# 7333.net
KiCad netlist of a schematic drawn in EAGLE
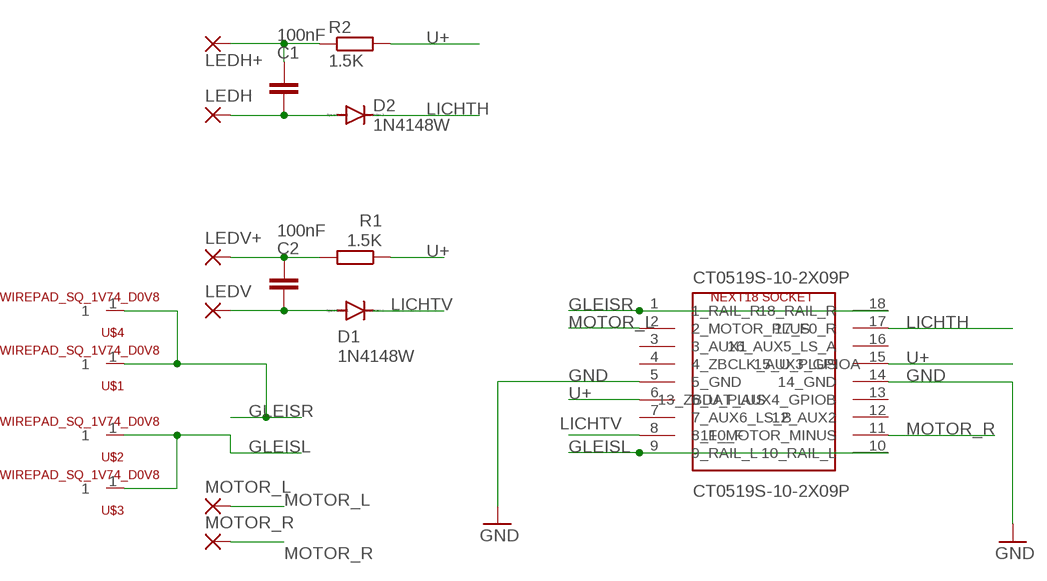
[diagram p0: schematic, sheet 1]

(export (version "E")
  (design (tool "Eeschema 10.0.6"))
  (components
    (comp (ref "C1")
      (value "100nF")
      (footprint "eagle-import:C0805")
      (libsource (lib "eagle-import") (part "C-EUC0805"))
    )
    (comp (ref "C2")
      (value "100nF")
      (footprint "eagle-import:C0805")
      (libsource (lib "eagle-import") (part "C-EUC0805"))
    )
    (comp (ref "CT0519S-10-2X09P")
      (value "CT0519S-10-2X09P")
      (footprint "eagle-import:NEXT18_SOCKET_GENERIC_VERIFY")
      (libsource (lib "eagle-import") (part "NEXT18_SOCKET-GENERIC-VERIFY"))
    )
    (comp (ref "D1")
      (value "1N4148W")
      (footprint "eagle-import:SOD123")
      (libsource (lib "eagle-import") (part "DIODE-SOD123"))
    )
    (comp (ref "D2")
      (value "1N4148W")
      (footprint "eagle-import:SOD123")
      (libsource (lib "eagle-import") (part "DIODE-SOD123"))
    )
    (comp (ref "LEDH")
      (value "SMD2")
      (footprint "eagle-import:SMD1,27-2,54")
      (libsource (lib "eagle-import") (part "SMD2"))
    )
    (comp (ref "LEDH+")
      (value "SMD2")
      (footprint "eagle-import:SMD1,27-2,54")
      (libsource (lib "eagle-import") (part "SMD2"))
    )
    (comp (ref "LEDV")
      (value "SMD2")
      (footprint "eagle-import:SMD1,27-2,54")
      (libsource (lib "eagle-import") (part "SMD2"))
    )
    (comp (ref "LEDV+")
      (value "SMD2")
      (footprint "eagle-import:SMD1,27-2,54")
      (libsource (lib "eagle-import") (part "SMD2"))
    )
    (comp (ref "MOTOR_L")
      (value "SMD5")
      (footprint "eagle-import:SMD2,54-5,08")
      (libsource (lib "eagle-import") (part "SMD5"))
    )
    (comp (ref "MOTOR_R")
      (value "SMD5")
      (footprint "eagle-import:SMD2,54-5,08")
      (libsource (lib "eagle-import") (part "SMD5"))
    )
    (comp (ref "R1")
      (value "1.5K")
      (footprint "eagle-import:M0805")
      (libsource (lib "eagle-import") (part "R-EU_M0805"))
    )
    (comp (ref "R2")
      (value "1.5K")
      (footprint "eagle-import:M0805")
      (libsource (lib "eagle-import") (part "R-EU_M0805"))
    )
    (comp (ref "U$1")
      (value "WIREPAD_SQ_1V74_D0V8")
      (footprint "eagle-import:WIREPAD_SQ_1V74_D0V8")
      (libsource (lib "eagle-import") (part "WIREPAD_SQ_1V74_D0V8"))
    )
    (comp (ref "U$2")
      (value "WIREPAD_SQ_1V74_D0V8")
      (footprint "eagle-import:WIREPAD_SQ_1V74_D0V8")
      (libsource (lib "eagle-import") (part "WIREPAD_SQ_1V74_D0V8"))
    )
    (comp (ref "U$3")
      (value "WIREPAD_SQ_1V74_D0V8")
      (footprint "eagle-import:WIREPAD_SQ_1V74_D0V8")
      (libsource (lib "eagle-import") (part "WIREPAD_SQ_1V74_D0V8"))
    )
    (comp (ref "U$4")
      (value "WIREPAD_SQ_1V74_D0V8")
      (footprint "eagle-import:WIREPAD_SQ_1V74_D0V8")
      (libsource (lib "eagle-import") (part "WIREPAD_SQ_1V74_D0V8"))
    )
  )
  (nets
    (net (code "1") (name "/GLEISL") (class "Default")
      (node (ref "CT0519S-10-2X09P") (pin "10") (pinfunction "10_RAIL_L_10") (pintype "passive"))
      (node (ref "CT0519S-10-2X09P") (pin "9") (pinfunction "9_RAIL_L_9") (pintype "passive"))
      (node (ref "U$2") (pin "1") (pinfunction "1_1") (pintype "passive"))
      (node (ref "U$3") (pin "1") (pinfunction "1_1") (pintype "passive"))
    )
    (net (code "2") (name "/GLEISR") (class "Default")
      (node (ref "CT0519S-10-2X09P") (pin "1") (pinfunction "1_RAIL_R_1") (pintype "passive"))
      (node (ref "CT0519S-10-2X09P") (pin "18") (pinfunction "18_RAIL_R_18") (pintype "passive"))
      (node (ref "U$1") (pin "1") (pinfunction "1_1") (pintype "passive"))
      (node (ref "U$4") (pin "1") (pinfunction "1_1") (pintype "passive"))
    )
    (net (code "3") (name "/LICHTH") (class "Default")
      (node (ref "CT0519S-10-2X09P") (pin "17") (pinfunction "17_F0_R_17") (pintype "passive"))
      (node (ref "D2") (pin "C") (pinfunction "C_C") (pintype "passive"))
    )
    (net (code "4") (name "/LICHTV") (class "Default")
      (node (ref "CT0519S-10-2X09P") (pin "8") (pinfunction "8_F0_F_8") (pintype "passive"))
      (node (ref "D1") (pin "C") (pinfunction "C_C") (pintype "passive"))
    )
    (net (code "5") (name "/MOTOR_L") (class "Default")
      (node (ref "CT0519S-10-2X09P") (pin "2") (pinfunction "2_MOTOR_PLUS_2") (pintype "passive"))
      (node (ref "MOTOR_L") (pin "1") (pinfunction "P_1") (pintype "passive"))
    )
    (net (code "6") (name "/MOTOR_R") (class "Default")
      (node (ref "CT0519S-10-2X09P") (pin "11") (pinfunction "11_MOTOR_MINUS_11") (pintype "passive"))
      (node (ref "MOTOR_R") (pin "1") (pinfunction "P_1") (pintype "passive"))
    )
    (net (code "7") (name "/U+") (class "Default")
      (node (ref "CT0519S-10-2X09P") (pin "15") (pinfunction "15_U_PLUS_15") (pintype "passive"))
      (node (ref "CT0519S-10-2X09P") (pin "6") (pinfunction "6_U_PLUS_6") (pintype "passive"))
      (node (ref "R1") (pin "1") (pinfunction "1_1") (pintype "passive"))
      (node (ref "R2") (pin "2") (pinfunction "2_2") (pintype "passive"))
    )
    (net (code "8") (name "GND") (class "Default")
      (node (ref "CT0519S-10-2X09P") (pin "14") (pinfunction "14_GND_14") (pintype "passive"))
      (node (ref "CT0519S-10-2X09P") (pin "5") (pinfunction "5_GND_5") (pintype "passive"))
    )
    (net (code "9") (name "Net-(LEDH+-P)") (class "Default")
      (node (ref "C1") (pin "1") (pinfunction "1_1") (pintype "passive"))
      (node (ref "LEDH+") (pin "1") (pinfunction "P_1") (pintype "passive"))
      (node (ref "R2") (pin "1") (pinfunction "1_1") (pintype "passive"))
    )
    (net (code "10") (name "Net-(LEDH-P)") (class "Default")
      (node (ref "C1") (pin "2") (pinfunction "2_2") (pintype "passive"))
      (node (ref "D2") (pin "A") (pinfunction "A_A") (pintype "passive"))
      (node (ref "LEDH") (pin "1") (pinfunction "P_1") (pintype "passive"))
    )
    (net (code "11") (name "Net-(LEDV+-P)") (class "Default")
      (node (ref "C2") (pin "1") (pinfunction "1_1") (pintype "passive"))
      (node (ref "LEDV+") (pin "1") (pinfunction "P_1") (pintype "passive"))
      (node (ref "R1") (pin "2") (pinfunction "2_2") (pintype "passive"))
    )
    (net (code "12") (name "Net-(LEDV-P)") (class "Default")
      (node (ref "C2") (pin "2") (pinfunction "2_2") (pintype "passive"))
      (node (ref "D1") (pin "A") (pinfunction "A_A") (pintype "passive"))
      (node (ref "LEDV") (pin "1") (pinfunction "P_1") (pintype "passive"))
    )
    (net (code "13") (name "unconnected-(CT0519S-10-2X09P-3_AUX1-Pad3)") (class "Default")
      (node (ref "CT0519S-10-2X09P") (pin "3") (pinfunction "3_AUX1_3") (pintype "passive"))
    )
    (net (code "14") (name "unconnected-(CT0519S-10-2X09P-4_ZBCLK_AUX3_GPIOA-Pad4)") (class "Default")
      (node (ref "CT0519S-10-2X09P") (pin "4") (pinfunction "4_ZBCLK_AUX3_GPIOA_4") (pintype "passive"))
    )
    (net (code "15") (name "unconnected-(CT0519S-10-2X09P-7_AUX6_LS_B-Pad7)") (class "Default")
      (node (ref "CT0519S-10-2X09P") (pin "7") (pinfunction "7_AUX6_LS_B_7") (pintype "passive"))
    )
    (net (code "16") (name "unconnected-(CT0519S-10-2X09P-12_AUX2-Pad12)") (class "Default")
      (node (ref "CT0519S-10-2X09P") (pin "12") (pinfunction "12_AUX2_12") (pintype "passive"))
    )
    (net (code "17") (name "unconnected-(CT0519S-10-2X09P-13_ZBDAT_AUX4_GPIOB-Pad13)") (class "Default")
      (node (ref "CT0519S-10-2X09P") (pin "13") (pinfunction "13_ZBDAT_AUX4_GPIOB_13") (pintype "passive"))
    )
    (net (code "18") (name "unconnected-(CT0519S-10-2X09P-16_AUX5_LS_A-Pad16)") (class "Default")
      (node (ref "CT0519S-10-2X09P") (pin "16") (pinfunction "16_AUX5_LS_A_16") (pintype "passive"))
    )
  )
)
